# arduino_cruise_control.net
KiCad netlist of a schematic drawn in EasyEDA
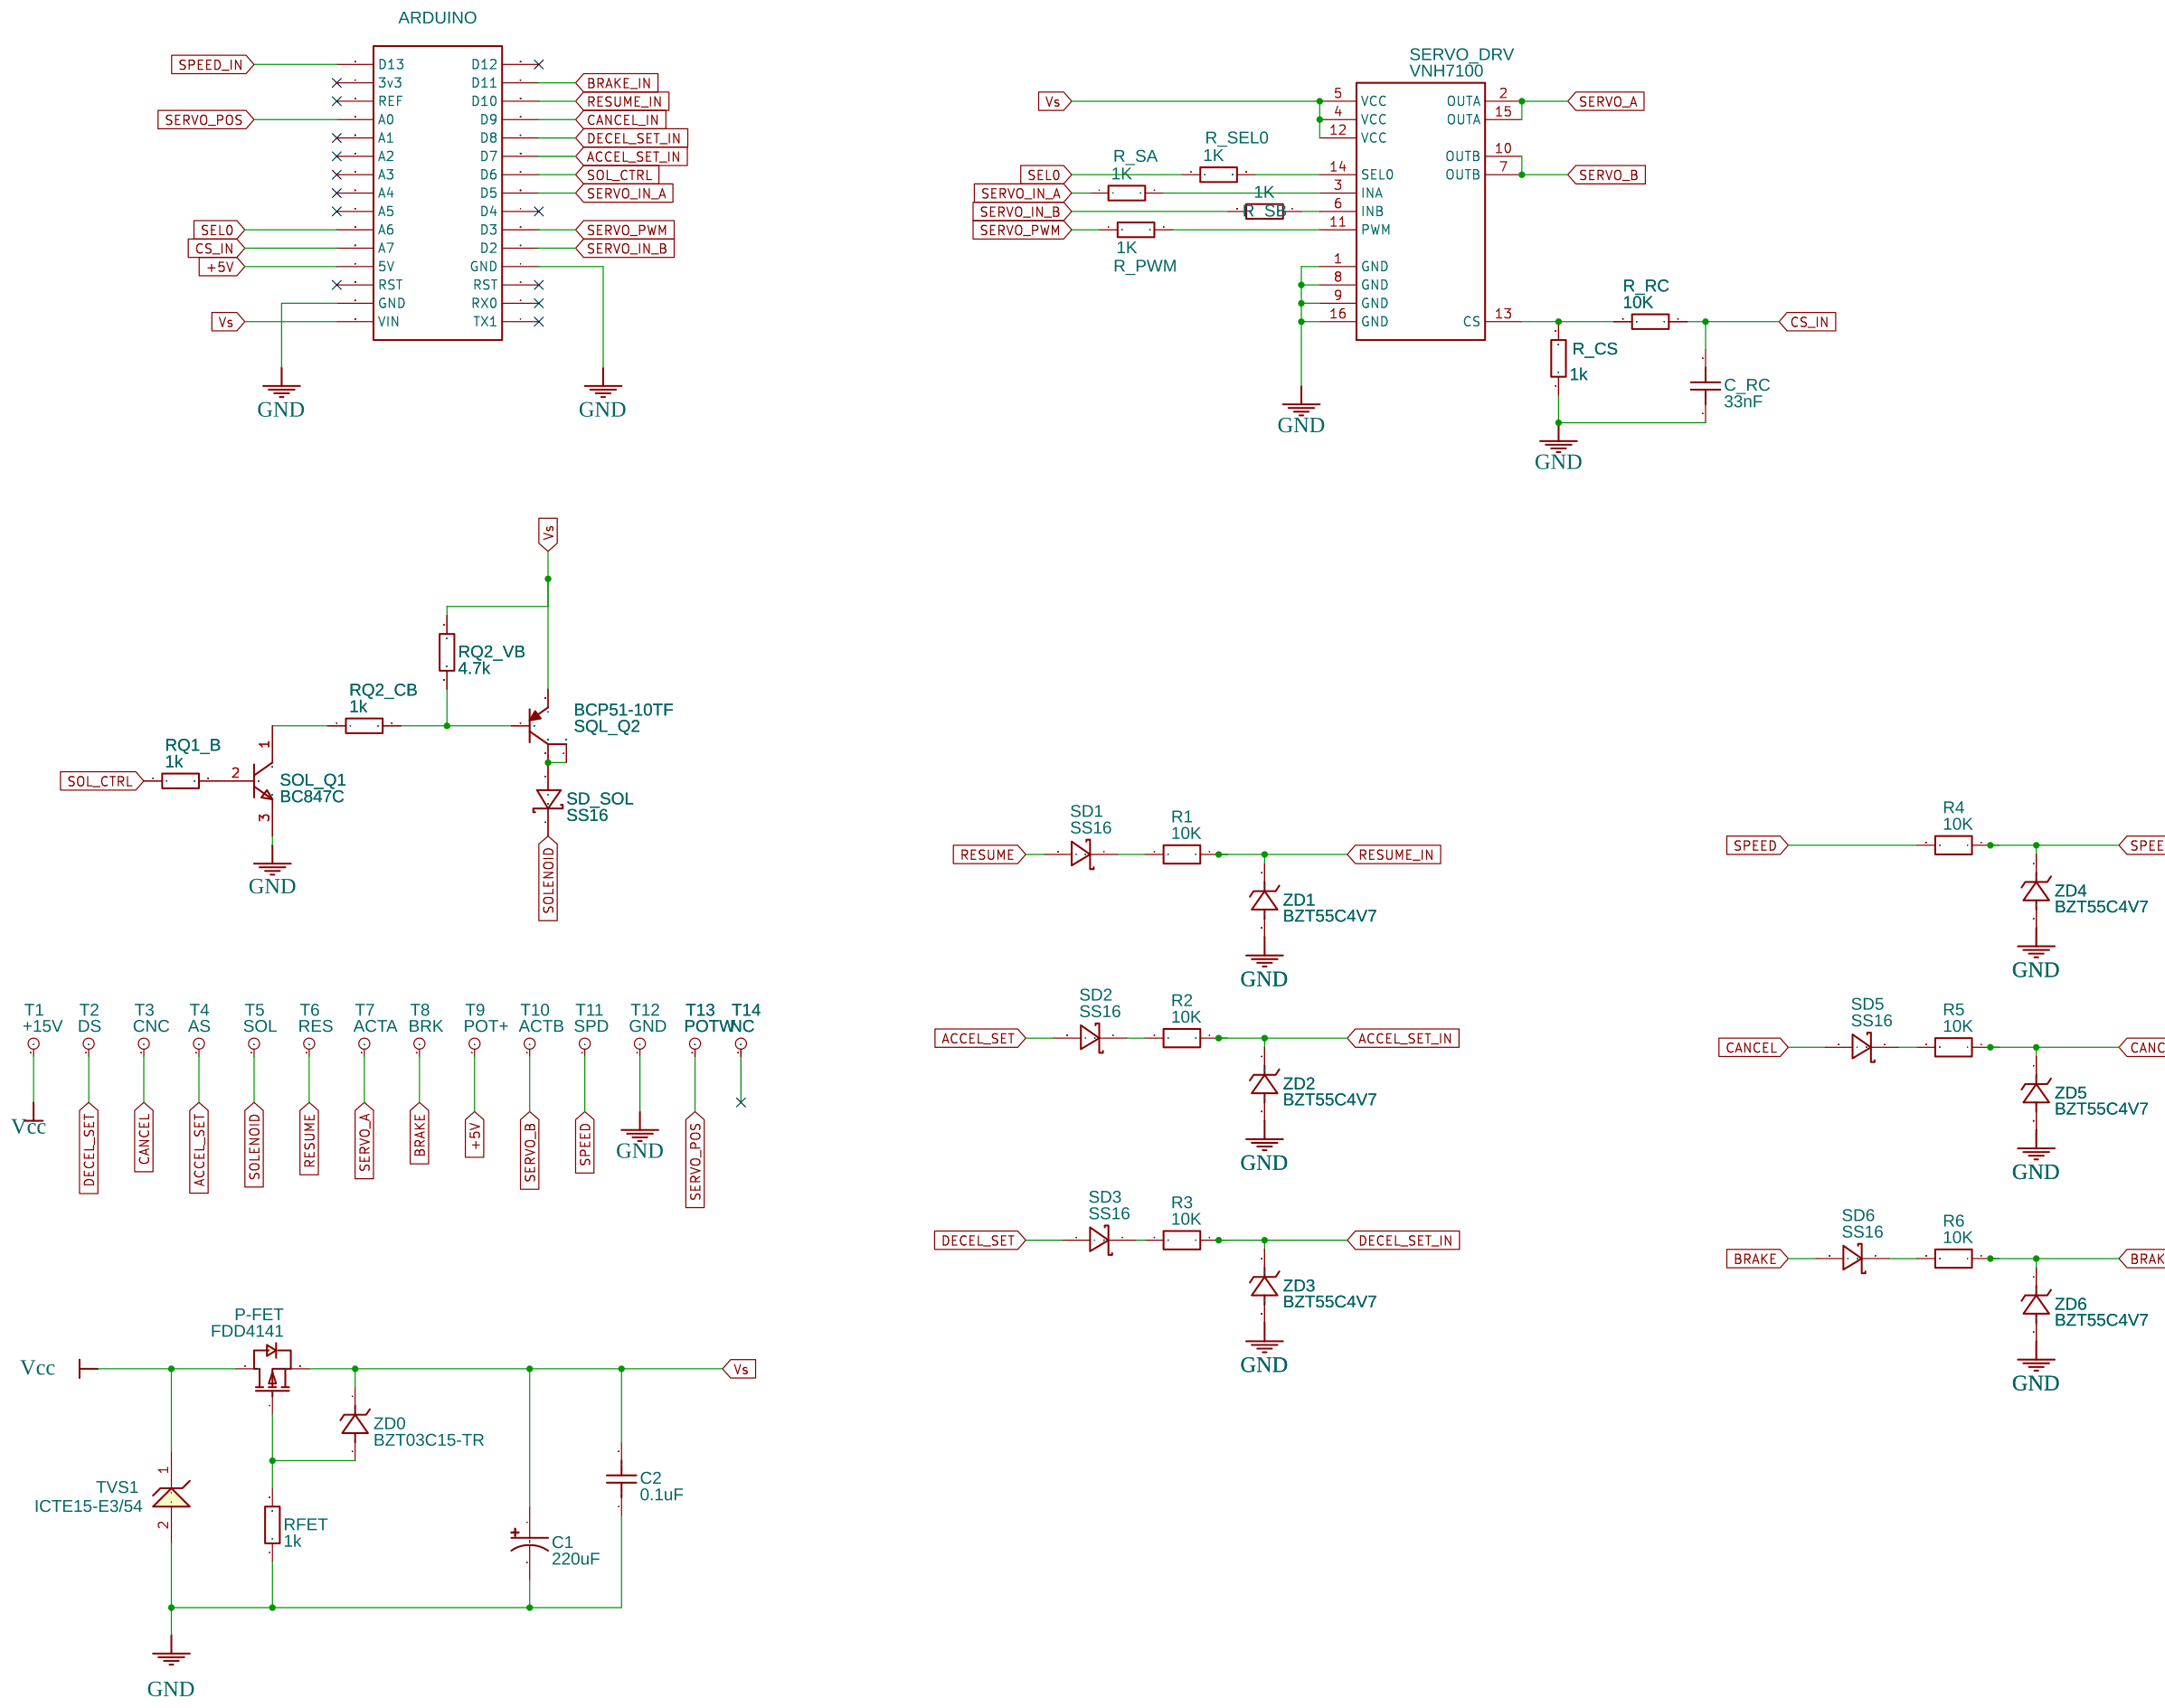
[diagram p0: schematic sheet]

(export (version "E")
  (design (tool "Eeschema 10.0.6"))
  (components
    (comp (ref "ARDUINO")
      (value "Arduino Nano Every")
      (fields (field (name "BOM_Manufacturer Part") "ABX00028") (field (name "BOM_Supplier Part") "3404690"))
      (libsource (lib "") (part "ARDUINO NANO EVERY SOLDER PADS SPEC.V2"))
    )
    (comp (ref "C1")
      (value "220uF")
      (fields
        (field (name "BOM_Manufacturer Part") "865060657012")
        (field (name "BOM_Supplier Part") "2466237")
      )
      (libsource (lib "") (part "EEEFT1H221GP"))
    )
    (comp (ref "C2")
      (value "0.1uF")
      (fields
        (field (name "BOM_Manufacturer Part") "C1206C104M5RACTU")
        (field (name "BOM_Supplier Part") "2581103")
      )
      (libsource (lib "") (part "TCC1206X7R225M250FT_1"))
    )
    (comp (ref "C_RC")
      (value "33nF")
      (fields
        (field (name "BOM_Manufacturer Part") "C1206X333K5RACTU")
        (field (name "BOM_Supplier Part") "2906070")
      )
      (libsource (lib "") (part "TCC1206X7R225M250FT"))
    )
    (comp (ref "P-FET")
      (value "FDD4141")
      (fields
        (field (name "BOM_Manufacturer Part") "FDD4141-F085")
        (field (name "BOM_Supplier Part") "2992319")
      )
      (libsource (lib "") (part "FDD4141_C140697"))
    )
    (comp (ref "R1")
      (value "10K")
      (fields
        (field (name "BOM_Manufacturer Part") "MCWF12P1002FTL")
        (field (name "BOM_Supplier Part") "2694438")
      )
      (libsource (lib "") (part "R_2512_EU"))
    )
    (comp (ref "R2")
      (value "10K")
      (fields
        (field (name "BOM_Manufacturer Part") "MCWF12P1002FTL")
        (field (name "BOM_Supplier Part") "2694438")
      )
      (libsource (lib "") (part "R_2512_EU"))
    )
    (comp (ref "R3")
      (value "10K")
      (fields
        (field (name "BOM_Manufacturer Part") "MCWF12P1002FTL")
        (field (name "BOM_Supplier Part") "2694438")
      )
      (libsource (lib "") (part "R_2512_EU"))
    )
    (comp (ref "R4")
      (value "10K")
      (fields
        (field (name "BOM_Manufacturer Part") "MCWF12P1002FTL")
        (field (name "BOM_Supplier Part") "2694438")
      )
      (libsource (lib "") (part "R_2512_EU"))
    )
    (comp (ref "R5")
      (value "10K")
      (fields
        (field (name "BOM_Manufacturer Part") "MCWF12P1002FTL")
        (field (name "BOM_Supplier Part") "2694438")
      )
      (libsource (lib "") (part "R_2512_EU"))
    )
    (comp (ref "R6")
      (value "10K")
      (fields
        (field (name "BOM_Manufacturer Part") "MCWF12P1002FTL")
        (field (name "BOM_Supplier Part") "2694438")
      )
      (libsource (lib "") (part "R_2512_EU"))
    )
    (comp (ref "RFET")
      (value "1k")
      (fields
        (field (name "BOM_Manufacturer Part") "CRM2512-FX-1001ELF")
        (field (name "BOM_Supplier Part") "2321763")
      )
      (libsource (lib "") (part "CF1/4W-1KΩ±5% T52_8"))
    )
    (comp (ref "RQ1_B")
      (value "1k")
      (fields
        (field (name "BOM_Manufacturer Part") "MCWF12P1001FTL")
        (field (name "BOM_Supplier Part") "2694437")
      )
      (libsource (lib "") (part "CF1/4W-1KΩ±5% T52"))
    )
    (comp (ref "RQ2_CB")
      (value "1k")
      (fields
        (field (name "BOM_Manufacturer Part") "MCWF12P1001FTL")
        (field (name "BOM_Supplier Part") "2694437")
      )
      (libsource (lib "") (part "CF1/4W-1KΩ±5% T52_2"))
    )
    (comp (ref "RQ2_VB")
      (value "4.7k")
      (fields
        (field (name "BOM_Manufacturer Part") "WCR1206-4K7FI")
        (field (name "BOM_Supplier Part") "1100209")
      )
      (libsource (lib "") (part "CF1/4W-1KΩ±5% T52_7"))
    )
    (comp (ref "R_CS")
      (value "1k")
      (fields
        (field (name "BOM_Manufacturer Part") "MCWF12P1001FTL")
        (field (name "BOM_Supplier Part") "2694437")
      )
      (libsource (lib "") (part "CF1/4W-1KΩ±5% T52_1"))
    )
    (comp (ref "R_PWM")
      (value "1K")
      (fields
        (field (name "BOM_Manufacturer Part") "MCWF12P1001FTL")
        (field (name "BOM_Supplier Part") "2694437")
      )
      (libsource (lib "") (part "CF1/4W-1KΩ±5% T52_6"))
    )
    (comp (ref "R_RC")
      (value "10K")
      (fields
        (field (name "BOM_Manufacturer Part") "MCWF12P1002FTL")
        (field (name "BOM_Supplier Part") "2694438")
      )
      (libsource (lib "") (part "CF1/4W-1KΩ±5% T52_3"))
    )
    (comp (ref "R_SA")
      (value "1K")
      (fields
        (field (name "BOM_Manufacturer Part") "MCWF12P1001FTL")
        (field (name "BOM_Supplier Part") "2694437")
      )
      (libsource (lib "") (part "CF1/4W-1KΩ±5% T52_5"))
    )
    (comp (ref "R_SB")
      (value "1K")
      (fields
        (field (name "BOM_Manufacturer Part") "MCWF12P1001FTL")
        (field (name "BOM_Supplier Part") "2694437")
      )
      (libsource (lib "") (part "CF1/4W-1KΩ±5% T52_9"))
    )
    (comp (ref "R_SEL0")
      (value "1K")
      (fields
        (field (name "BOM_Manufacturer Part") "MCWF12P1001FTL")
        (field (name "BOM_Supplier Part") "2694437")
      )
      (libsource (lib "") (part "CF1/4W-1KΩ±5% T52_4"))
    )
    (comp (ref "SD1")
      (value "SS16")
      (fields (field (name "BOM_Manufacturer Part") "SS16.") (field (name "BOM_Supplier Part") "2101190"))
      (libsource (lib "") (part "SS16-E3/61T"))
    )
    (comp (ref "SD2")
      (value "SS16")
      (fields (field (name "BOM_Manufacturer Part") "SS16.") (field (name "BOM_Supplier Part") "2101190"))
      (libsource (lib "") (part "SS16-E3/61T"))
    )
    (comp (ref "SD3")
      (value "SS16")
      (fields (field (name "BOM_Manufacturer Part") "SS16.") (field (name "BOM_Supplier Part") "2101190"))
      (libsource (lib "") (part "SS16-E3/61T"))
    )
    (comp (ref "SD5")
      (value "SS16")
      (fields (field (name "BOM_Manufacturer Part") "SS16.") (field (name "BOM_Supplier Part") "2101190"))
      (libsource (lib "") (part "SS16-E3/61T"))
    )
    (comp (ref "SD6")
      (value "SS16")
      (fields (field (name "BOM_Manufacturer Part") "SS16.") (field (name "BOM_Supplier Part") "2101190"))
      (libsource (lib "") (part "SS16-E3/61T"))
    )
    (comp (ref "SD_SOL")
      (value "SS16")
      (fields (field (name "BOM_Manufacturer Part") "SS16.") (field (name "BOM_Supplier Part") "2101190"))
      (libsource (lib "") (part "SS16-E3/61T_1"))
    )
    (comp (ref "SERVO_DRV")
      (value "VNH7100")
      (fields
        (field (name "BOM_Manufacturer Part") "VNH7100ASTR")
        (field (name "BOM_Supplier Part") "2797972")
      )
      (libsource (lib "") (part "VNH7100"))
    )
    (comp (ref "SOL_Q1")
      (value "BC847C")
      (fields
        (field (name "BOM_Manufacturer Part") "BC847C,215")
        (field (name "BOM_Supplier Part") "1081235")
      )
      (libsource (lib "") (part "BC547C"))
    )
    (comp (ref "SQL_Q2")
      (value "BCP51-10TF")
      (fields (field (name "BOM_Supplier Part") "3212664"))
      (libsource (lib "") (part "BCP51-10TF"))
    )
    (comp (ref "T1") (value "+15V") (libsource (lib "") (part "PAD_TERMINAL-32MIL_SQUARE")))
    (comp (ref "T2") (value "DS") (libsource (lib "") (part "PAD_TERMINAL-32MIL_SQUARE")))
    (comp (ref "T3") (value "CNC") (libsource (lib "") (part "PAD_TERMINAL-32MIL_SQUARE")))
    (comp (ref "T4") (value "AS") (libsource (lib "") (part "PAD_TERMINAL-32MIL_SQUARE")))
    (comp (ref "T5") (value "SOL") (libsource (lib "") (part "PAD_TERMINAL-32MIL_SQUARE")))
    (comp (ref "T6") (value "RES") (libsource (lib "") (part "PAD_TERMINAL-32MIL_SQUARE")))
    (comp (ref "T7") (value "ACTA") (libsource (lib "") (part "PAD_TERMINAL-32MIL_SQUARE")))
    (comp (ref "T8") (value "BRK") (libsource (lib "") (part "PAD_TERMINAL-32MIL_SQUARE")))
    (comp (ref "T9") (value "POT+") (libsource (lib "") (part "PAD_TERMINAL-32MIL_SQUARE")))
    (comp (ref "T10") (value "ACTB") (libsource (lib "") (part "PAD_TERMINAL-32MIL_SQUARE")))
    (comp (ref "T11") (value "SPD") (libsource (lib "") (part "PAD_TERMINAL-32MIL_SQUARE")))
    (comp (ref "T12") (value "GND") (libsource (lib "") (part "PAD_TERMINAL-32MIL_SQUARE")))
    (comp (ref "T13") (value "POTW") (libsource (lib "") (part "PAD_TERMINAL-32MIL_SQUARE")))
    (comp (ref "T14") (value "NC") (libsource (lib "") (part "PAD_TERMINAL-32MIL_SQUARE")))
    (comp (ref "TVS1")
      (value "ICTE15-E3/54")
      (fields (field (name "BOM_Supplier Part") "2335234"))
      (libsource (lib "") (part "1N6377"))
    )
    (comp (ref "ZD0")
      (value "BZT03C15-TR")
      (fields (field (name "BOM_Supplier Part") "9398317"))
      (libsource (lib "") (part "BZV55-C9V1,135"))
    )
    (comp (ref "ZD1")
      (value "BZT55C4V7")
      (fields
        (field (name "BOM_Manufacturer Part") "BZT55C4V7-GS08")
        (field (name "BOM_Supplier Part") "1617757")
      )
      (libsource (lib "") (part "BZV55-C5V1,135"))
    )
    (comp (ref "ZD2")
      (value "BZT55C4V7")
      (fields
        (field (name "BOM_Manufacturer Part") "BZT55C4V7-GS08")
        (field (name "BOM_Supplier Part") "1617757")
      )
      (libsource (lib "") (part "BZV55-C5V1,135"))
    )
    (comp (ref "ZD3")
      (value "BZT55C4V7")
      (fields
        (field (name "BOM_Manufacturer Part") "BZT55C4V7-GS08")
        (field (name "BOM_Supplier Part") "1617757")
      )
      (libsource (lib "") (part "BZV55-C5V1,135"))
    )
    (comp (ref "ZD4")
      (value "BZT55C4V7")
      (fields
        (field (name "BOM_Manufacturer Part") "BZT55C4V7-GS08")
        (field (name "BOM_Supplier Part") "1617757")
      )
      (libsource (lib "") (part "BZV55-C5V1,135"))
    )
    (comp (ref "ZD5")
      (value "BZT55C4V7")
      (fields
        (field (name "BOM_Manufacturer Part") "BZT55C4V7-GS08")
        (field (name "BOM_Supplier Part") "1617757")
      )
      (libsource (lib "") (part "BZV55-C5V1,135"))
    )
    (comp (ref "ZD6")
      (value "BZT55C4V7")
      (fields
        (field (name "BOM_Manufacturer Part") "BZT55C4V7-GS08")
        (field (name "BOM_Supplier Part") "1617757")
      )
      (libsource (lib "") (part "BZV55-C5V1,135"))
    )
  )
  (nets
    (net (code "1") (name "+5V") (class "Default")
      (node (ref "ARDUINO") (pin "27") (pinfunction "5V_27") (pintype "unspecified"))
      (node (ref "T9") (pin "P") (pinfunction "P_P") (pintype "unspecified"))
    )
    (net (code "2") (name "ACCEL_SET") (class "Default")
      (node (ref "SD2") (pin "2") (pinfunction "A_2") (pintype "unspecified"))
      (node (ref "T4") (pin "P") (pinfunction "P_P") (pintype "unspecified"))
    )
    (net (code "3") (name "ACCEL_SET_IN") (class "Default")
      (node (ref "ARDUINO") (pin "10") (pinfunction "D7_10") (pintype "unspecified"))
      (node (ref "R2") (pin "1") (pinfunction "1_1") (pintype "unspecified"))
      (node (ref "ZD2") (pin "1") (pinfunction "K_1") (pintype "unspecified"))
    )
    (net (code "4") (name "BRAKE") (class "Default")
      (node (ref "SD6") (pin "2") (pinfunction "A_2") (pintype "unspecified"))
      (node (ref "T8") (pin "P") (pinfunction "P_P") (pintype "unspecified"))
    )
    (net (code "5") (name "BRAKE_IN") (class "Default")
      (node (ref "ARDUINO") (pin "14") (pinfunction "D11_14") (pintype "unspecified"))
      (node (ref "R6") (pin "1") (pinfunction "1_1") (pintype "unspecified"))
      (node (ref "ZD6") (pin "1") (pinfunction "K_1") (pintype "unspecified"))
    )
    (net (code "6") (name "CANCEL") (class "Default")
      (node (ref "SD5") (pin "2") (pinfunction "A_2") (pintype "unspecified"))
      (node (ref "T3") (pin "P") (pinfunction "P_P") (pintype "unspecified"))
    )
    (net (code "7") (name "CANCEL_IN") (class "Default")
      (node (ref "ARDUINO") (pin "12") (pinfunction "D9_12") (pintype "unspecified"))
      (node (ref "R5") (pin "1") (pinfunction "1_1") (pintype "unspecified"))
      (node (ref "ZD5") (pin "1") (pinfunction "K_1") (pintype "unspecified"))
    )
    (net (code "8") (name "CS_IN") (class "Default")
      (node (ref "ARDUINO") (pin "26") (pinfunction "A7_26") (pintype "unspecified"))
      (node (ref "C_RC") (pin "2") (pinfunction "2_2") (pintype "unspecified"))
      (node (ref "R_RC") (pin "1") (pinfunction "1_1") (pintype "unspecified"))
    )
    (net (code "9") (name "DECEL_SET") (class "Default")
      (node (ref "SD3") (pin "2") (pinfunction "A_2") (pintype "unspecified"))
      (node (ref "T2") (pin "P") (pinfunction "P_P") (pintype "unspecified"))
    )
    (net (code "10") (name "DECEL_SET_IN") (class "Default")
      (node (ref "ARDUINO") (pin "11") (pinfunction "D8_11") (pintype "unspecified"))
      (node (ref "R3") (pin "1") (pinfunction "1_1") (pintype "unspecified"))
      (node (ref "ZD3") (pin "1") (pinfunction "K_1") (pintype "unspecified"))
    )
    (net (code "11") (name "GND") (class "Default")
      (node (ref "ARDUINO") (pin "29") (pinfunction "GND_29") (pintype "unspecified"))
      (node (ref "ARDUINO") (pin "4") (pinfunction "GND_4") (pintype "unspecified"))
      (node (ref "C1") (pin "2") (pinfunction "2_2") (pintype "unspecified"))
      (node (ref "C2") (pin "1") (pinfunction "1_1") (pintype "unspecified"))
      (node (ref "C_RC") (pin "1") (pinfunction "1_1") (pintype "unspecified"))
      (node (ref "RFET") (pin "1") (pinfunction "1_1") (pintype "unspecified"))
      (node (ref "R_CS") (pin "1") (pinfunction "1_1") (pintype "unspecified"))
      (node (ref "SERVO_DRV") (pin "1") (pinfunction "GND_1") (pintype "passive"))
      (node (ref "SERVO_DRV") (pin "16") (pinfunction "GND_16") (pintype "passive"))
      (node (ref "SERVO_DRV") (pin "8") (pinfunction "GND_8") (pintype "passive"))
      (node (ref "SERVO_DRV") (pin "9") (pinfunction "GND_9") (pintype "passive"))
      (node (ref "SOL_Q1") (pin "3") (pinfunction "E_3") (pintype "unspecified"))
      (node (ref "T12") (pin "P") (pinfunction "P_P") (pintype "unspecified"))
      (node (ref "TVS1") (pin "2") (pinfunction "A_2") (pintype "unspecified"))
      (node (ref "ZD1") (pin "2") (pinfunction "A_2") (pintype "unspecified"))
      (node (ref "ZD2") (pin "2") (pinfunction "A_2") (pintype "unspecified"))
      (node (ref "ZD3") (pin "2") (pinfunction "A_2") (pintype "unspecified"))
      (node (ref "ZD4") (pin "2") (pinfunction "A_2") (pintype "unspecified"))
      (node (ref "ZD5") (pin "2") (pinfunction "A_2") (pintype "unspecified"))
      (node (ref "ZD6") (pin "2") (pinfunction "A_2") (pintype "unspecified"))
    )
    (net (code "12") (name "Net-(P-FET-G)") (class "Default")
      (node (ref "P-FET") (pin "1") (pinfunction "G_1") (pintype "unspecified"))
      (node (ref "RFET") (pin "2") (pinfunction "2_2") (pintype "unspecified"))
      (node (ref "ZD0") (pin "2") (pinfunction "A_2") (pintype "unspecified"))
    )
    (net (code "13") (name "Net-(SD1-C)") (class "Default")
      (node (ref "R1") (pin "2") (pinfunction "2_2") (pintype "unspecified"))
      (node (ref "SD1") (pin "1") (pinfunction "C_1") (pintype "unspecified"))
    )
    (net (code "14") (name "Net-(SD2-C)") (class "Default")
      (node (ref "R2") (pin "2") (pinfunction "2_2") (pintype "unspecified"))
      (node (ref "SD2") (pin "1") (pinfunction "C_1") (pintype "unspecified"))
    )
    (net (code "15") (name "Net-(SD3-C)") (class "Default")
      (node (ref "R3") (pin "2") (pinfunction "2_2") (pintype "unspecified"))
      (node (ref "SD3") (pin "1") (pinfunction "C_1") (pintype "unspecified"))
    )
    (net (code "16") (name "Net-(SD5-C)") (class "Default")
      (node (ref "R5") (pin "2") (pinfunction "2_2") (pintype "unspecified"))
      (node (ref "SD5") (pin "1") (pinfunction "C_1") (pintype "unspecified"))
    )
    (net (code "17") (name "Net-(SD6-C)") (class "Default")
      (node (ref "R6") (pin "2") (pinfunction "2_2") (pintype "unspecified"))
      (node (ref "SD6") (pin "1") (pinfunction "C_1") (pintype "unspecified"))
    )
    (net (code "18") (name "Net-(SD_SOL-A)") (class "Default")
      (node (ref "SD_SOL") (pin "2") (pinfunction "A_2") (pintype "unspecified"))
      (node (ref "SQL_Q2") (pin "2") (pinfunction "C_2") (pintype "input"))
      (node (ref "SQL_Q2") (pin "4") (pinfunction "C_4") (pintype "input"))
    )
    (net (code "19") (name "Net-(SERVO_DRV-CS)") (class "Default")
      (node (ref "R_CS") (pin "2") (pinfunction "2_2") (pintype "unspecified"))
      (node (ref "R_RC") (pin "2") (pinfunction "2_2") (pintype "unspecified"))
      (node (ref "SERVO_DRV") (pin "13") (pinfunction "CS_13") (pintype "output"))
    )
    (net (code "20") (name "Net-(SERVO_DRV-INA)") (class "Default")
      (node (ref "R_SA") (pin "2") (pinfunction "2_2") (pintype "unspecified"))
      (node (ref "SERVO_DRV") (pin "3") (pinfunction "INA_3") (pintype "input"))
    )
    (net (code "21") (name "Net-(SERVO_DRV-INB)") (class "Default")
      (node (ref "R_SB") (pin "1") (pinfunction "1_1") (pintype "unspecified"))
      (node (ref "SERVO_DRV") (pin "6") (pinfunction "INB_6") (pintype "input"))
    )
    (net (code "22") (name "Net-(SERVO_DRV-PWM)") (class "Default")
      (node (ref "R_PWM") (pin "2") (pinfunction "2_2") (pintype "unspecified"))
      (node (ref "SERVO_DRV") (pin "11") (pinfunction "PWM_11") (pintype "input"))
    )
    (net (code "23") (name "Net-(SERVO_DRV-SEL0)") (class "Default")
      (node (ref "R_SEL0") (pin "2") (pinfunction "2_2") (pintype "unspecified"))
      (node (ref "SERVO_DRV") (pin "14") (pinfunction "SEL0_14") (pintype "bidirectional"))
    )
    (net (code "24") (name "Net-(SOL_Q1-B)") (class "Default")
      (node (ref "RQ1_B") (pin "2") (pinfunction "2_2") (pintype "unspecified"))
      (node (ref "SOL_Q1") (pin "2") (pinfunction "B_2") (pintype "unspecified"))
    )
    (net (code "25") (name "Net-(SOL_Q1-C)") (class "Default")
      (node (ref "RQ2_CB") (pin "1") (pinfunction "1_1") (pintype "unspecified"))
      (node (ref "SOL_Q1") (pin "1") (pinfunction "C_1") (pintype "unspecified"))
    )
    (net (code "26") (name "Net-(SQL_Q2-B)") (class "Default")
      (node (ref "RQ2_CB") (pin "2") (pinfunction "2_2") (pintype "unspecified"))
      (node (ref "RQ2_VB") (pin "2") (pinfunction "2_2") (pintype "unspecified"))
      (node (ref "SQL_Q2") (pin "1") (pinfunction "B_1") (pintype "input"))
    )
    (net (code "27") (name "RESUME") (class "Default")
      (node (ref "SD1") (pin "2") (pinfunction "A_2") (pintype "unspecified"))
      (node (ref "T6") (pin "P") (pinfunction "P_P") (pintype "unspecified"))
    )
    (net (code "28") (name "RESUME_IN") (class "Default")
      (node (ref "ARDUINO") (pin "13") (pinfunction "D10_13") (pintype "unspecified"))
      (node (ref "R1") (pin "1") (pinfunction "1_1") (pintype "unspecified"))
      (node (ref "ZD1") (pin "1") (pinfunction "K_1") (pintype "unspecified"))
    )
    (net (code "29") (name "SEL0") (class "Default")
      (node (ref "ARDUINO") (pin "25") (pinfunction "A6_25") (pintype "unspecified"))
      (node (ref "R_SEL0") (pin "1") (pinfunction "1_1") (pintype "unspecified"))
    )
    (net (code "30") (name "SERVO_A") (class "Default")
      (node (ref "SERVO_DRV") (pin "15") (pinfunction "OUTA_15") (pintype "passive"))
      (node (ref "SERVO_DRV") (pin "2") (pinfunction "OUTA_2") (pintype "passive"))
      (node (ref "T7") (pin "P") (pinfunction "P_P") (pintype "unspecified"))
    )
    (net (code "31") (name "SERVO_B") (class "Default")
      (node (ref "SERVO_DRV") (pin "10") (pinfunction "OUTB_10") (pintype "passive"))
      (node (ref "SERVO_DRV") (pin "7") (pinfunction "OUTB_7") (pintype "passive"))
      (node (ref "T10") (pin "P") (pinfunction "P_P") (pintype "unspecified"))
    )
    (net (code "32") (name "SERVO_IN_A") (class "Default")
      (node (ref "ARDUINO") (pin "8") (pinfunction "D5_8") (pintype "unspecified"))
      (node (ref "R_SA") (pin "1") (pinfunction "1_1") (pintype "unspecified"))
    )
    (net (code "33") (name "SERVO_IN_B") (class "Default")
      (node (ref "ARDUINO") (pin "5") (pinfunction "D2_5") (pintype "unspecified"))
      (node (ref "R_SB") (pin "2") (pinfunction "2_2") (pintype "unspecified"))
    )
    (net (code "34") (name "SERVO_POS") (class "Default")
      (node (ref "ARDUINO") (pin "19") (pinfunction "A0_19") (pintype "unspecified"))
      (node (ref "T13") (pin "P") (pinfunction "P_P") (pintype "unspecified"))
    )
    (net (code "35") (name "SERVO_PWM") (class "Default")
      (node (ref "ARDUINO") (pin "6") (pinfunction "D3_6") (pintype "unspecified"))
      (node (ref "R_PWM") (pin "1") (pinfunction "1_1") (pintype "unspecified"))
    )
    (net (code "36") (name "SOLENOID") (class "Default")
      (node (ref "SD_SOL") (pin "1") (pinfunction "C_1") (pintype "unspecified"))
      (node (ref "T5") (pin "P") (pinfunction "P_P") (pintype "unspecified"))
    )
    (net (code "37") (name "SOL_CTRL") (class "Default")
      (node (ref "ARDUINO") (pin "9") (pinfunction "D6_9") (pintype "unspecified"))
      (node (ref "RQ1_B") (pin "1") (pinfunction "1_1") (pintype "unspecified"))
    )
    (net (code "38") (name "SPEED") (class "Default")
      (node (ref "R4") (pin "2") (pinfunction "2_2") (pintype "unspecified"))
      (node (ref "T11") (pin "P") (pinfunction "P_P") (pintype "unspecified"))
    )
    (net (code "39") (name "SPEED_IN") (class "Default")
      (node (ref "ARDUINO") (pin "16") (pinfunction "D13_16") (pintype "unspecified"))
      (node (ref "R4") (pin "1") (pinfunction "1_1") (pintype "unspecified"))
      (node (ref "ZD4") (pin "1") (pinfunction "K_1") (pintype "unspecified"))
    )
    (net (code "40") (name "Vcc") (class "Default")
      (node (ref "P-FET") (pin "2") (pinfunction "D_2") (pintype "unspecified"))
      (node (ref "T1") (pin "P") (pinfunction "P_P") (pintype "unspecified"))
      (node (ref "TVS1") (pin "1") (pinfunction "K_1") (pintype "unspecified"))
    )
    (net (code "41") (name "Vs") (class "Default")
      (node (ref "ARDUINO") (pin "30") (pinfunction "VIN_30") (pintype "unspecified"))
      (node (ref "C1") (pin "1") (pinfunction "1_1") (pintype "unspecified"))
      (node (ref "C2") (pin "2") (pinfunction "2_2") (pintype "unspecified"))
      (node (ref "P-FET") (pin "3") (pinfunction "S_3") (pintype "unspecified"))
      (node (ref "RQ2_VB") (pin "1") (pinfunction "1_1") (pintype "unspecified"))
      (node (ref "SERVO_DRV") (pin "12") (pinfunction "VCC_12") (pintype "passive"))
      (node (ref "SERVO_DRV") (pin "4") (pinfunction "VCC_4") (pintype "passive"))
      (node (ref "SERVO_DRV") (pin "5") (pinfunction "VCC_5") (pintype "passive"))
      (node (ref "SQL_Q2") (pin "3") (pinfunction "E_3") (pintype "input"))
      (node (ref "ZD0") (pin "1") (pinfunction "K_1") (pintype "unspecified"))
    )
    (net (code "42") (name "unconnected-(ARDUINO-3v3-Pad17)") (class "Default")
      (node (ref "ARDUINO") (pin "17") (pinfunction "3v3_17") (pintype "unspecified+no_connect"))
    )
    (net (code "43") (name "unconnected-(ARDUINO-A1-Pad20)") (class "Default")
      (node (ref "ARDUINO") (pin "20") (pinfunction "A1_20") (pintype "unspecified+no_connect"))
    )
    (net (code "44") (name "unconnected-(ARDUINO-A2-Pad21)") (class "Default")
      (node (ref "ARDUINO") (pin "21") (pinfunction "A2_21") (pintype "unspecified+no_connect"))
    )
    (net (code "45") (name "unconnected-(ARDUINO-A3-Pad22)") (class "Default")
      (node (ref "ARDUINO") (pin "22") (pinfunction "A3_22") (pintype "unspecified+no_connect"))
    )
    (net (code "46") (name "unconnected-(ARDUINO-A4-Pad23)") (class "Default")
      (node (ref "ARDUINO") (pin "23") (pinfunction "A4_23") (pintype "unspecified+no_connect"))
    )
    (net (code "47") (name "unconnected-(ARDUINO-A5-Pad24)") (class "Default")
      (node (ref "ARDUINO") (pin "24") (pinfunction "A5_24") (pintype "unspecified+no_connect"))
    )
    (net (code "48") (name "unconnected-(ARDUINO-D4-Pad7)") (class "Default")
      (node (ref "ARDUINO") (pin "7") (pinfunction "D4_7") (pintype "unspecified+no_connect"))
    )
    (net (code "49") (name "unconnected-(ARDUINO-D12-Pad15)") (class "Default")
      (node (ref "ARDUINO") (pin "15") (pinfunction "D12_15") (pintype "unspecified+no_connect"))
    )
    (net (code "50") (name "unconnected-(ARDUINO-REF-Pad18)") (class "Default")
      (node (ref "ARDUINO") (pin "18") (pinfunction "REF_18") (pintype "unspecified+no_connect"))
    )
    (net (code "51") (name "unconnected-(ARDUINO-RST-Pad3)") (class "Default")
      (node (ref "ARDUINO") (pin "3") (pinfunction "RST_3") (pintype "unspecified+no_connect"))
    )
    (net (code "52") (name "unconnected-(ARDUINO-RST-Pad28)") (class "Default")
      (node (ref "ARDUINO") (pin "28") (pinfunction "RST_28") (pintype "unspecified+no_connect"))
    )
    (net (code "53") (name "unconnected-(ARDUINO-RX0-Pad2)") (class "Default")
      (node (ref "ARDUINO") (pin "2") (pinfunction "RX0_2") (pintype "unspecified+no_connect"))
    )
    (net (code "54") (name "unconnected-(ARDUINO-TX1-Pad1)") (class "Default")
      (node (ref "ARDUINO") (pin "1") (pinfunction "TX1_1") (pintype "unspecified+no_connect"))
    )
    (net (code "55") (name "unconnected-(T14-PadP)") (class "Default")
      (node (ref "T14") (pin "P") (pinfunction "P_P") (pintype "unspecified+no_connect"))
    )
  )
)
